# grbl-cnc3ax-nano.net
KiCad netlist of a schematic drawn in EAGLE
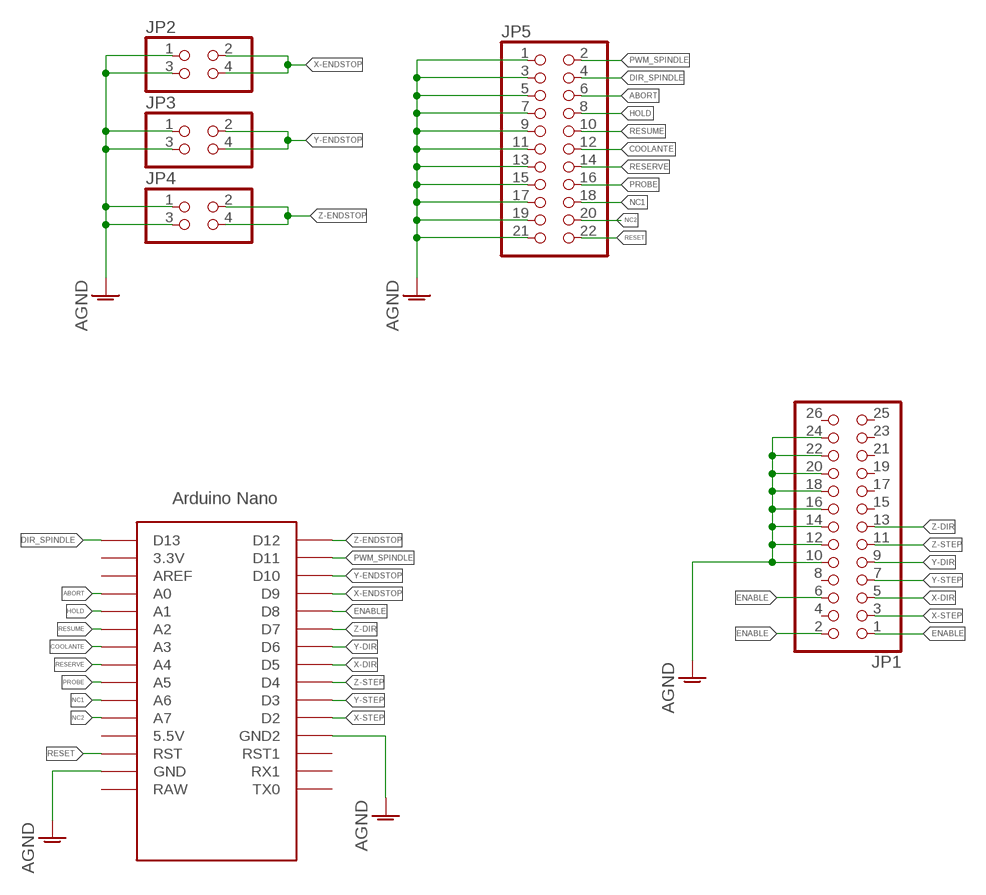
[diagram p0: schematic, sheet 1]

(export (version "E")
  (design (tool "Eeschema 10.0.6"))
  (components
    (comp (ref "JP1")
      (value "PINHD-2X13")
      (footprint "eagle-import:2X13")
      (libsource (lib "eagle-import") (part "PINHD-2X13"))
    )
    (comp (ref "JP2")
      (value "PINHD-2X2")
      (footprint "eagle-import:2X02")
      (libsource (lib "eagle-import") (part "PINHD-2X2"))
    )
    (comp (ref "JP3")
      (value "PINHD-2X2")
      (footprint "eagle-import:2X02")
      (libsource (lib "eagle-import") (part "PINHD-2X2"))
    )
    (comp (ref "JP4")
      (value "PINHD-2X2")
      (footprint "eagle-import:2X02")
      (libsource (lib "eagle-import") (part "PINHD-2X2"))
    )
    (comp (ref "JP5")
      (value "PINHD-2X11")
      (footprint "eagle-import:2X11")
      (libsource (lib "eagle-import") (part "PINHD-2X11"))
    )
    (comp (ref "U$1")
      (value "NANO")
      (footprint "eagle-import:NANO")
      (libsource (lib "eagle-import") (part "NANO"))
    )
  )
  (nets
    (net (code "1") (name "ABORT") (class "Default")
      (node (ref "JP5") (pin "6") (pinfunction "6_6") (pintype "passive"))
      (node (ref "U$1") (pin "A0") (pinfunction "A0_A0") (pintype "bidirectional"))
    )
    (net (code "2") (name "AGND") (class "Default")
      (node (ref "JP1") (pin "10") (pinfunction "10_10") (pintype "passive"))
      (node (ref "JP1") (pin "12") (pinfunction "12_12") (pintype "passive"))
      (node (ref "JP1") (pin "14") (pinfunction "14_14") (pintype "passive"))
      (node (ref "JP1") (pin "16") (pinfunction "16_16") (pintype "passive"))
      (node (ref "JP1") (pin "18") (pinfunction "18_18") (pintype "passive"))
      (node (ref "JP1") (pin "20") (pinfunction "20_20") (pintype "passive"))
      (node (ref "JP1") (pin "22") (pinfunction "22_22") (pintype "passive"))
      (node (ref "JP1") (pin "24") (pinfunction "24_24") (pintype "passive"))
      (node (ref "JP2") (pin "1") (pinfunction "1_1") (pintype "passive"))
      (node (ref "JP2") (pin "3") (pinfunction "3_3") (pintype "passive"))
      (node (ref "JP3") (pin "1") (pinfunction "1_1") (pintype "passive"))
      (node (ref "JP3") (pin "3") (pinfunction "3_3") (pintype "passive"))
      (node (ref "JP4") (pin "1") (pinfunction "1_1") (pintype "passive"))
      (node (ref "JP4") (pin "3") (pinfunction "3_3") (pintype "passive"))
      (node (ref "JP5") (pin "1") (pinfunction "1_1") (pintype "passive"))
      (node (ref "JP5") (pin "11") (pinfunction "11_11") (pintype "passive"))
      (node (ref "JP5") (pin "13") (pinfunction "13_13") (pintype "passive"))
      (node (ref "JP5") (pin "15") (pinfunction "15_15") (pintype "passive"))
      (node (ref "JP5") (pin "17") (pinfunction "17_17") (pintype "passive"))
      (node (ref "JP5") (pin "19") (pinfunction "19_19") (pintype "passive"))
      (node (ref "JP5") (pin "21") (pinfunction "21_21") (pintype "passive"))
      (node (ref "JP5") (pin "3") (pinfunction "3_3") (pintype "passive"))
      (node (ref "JP5") (pin "5") (pinfunction "5_5") (pintype "passive"))
      (node (ref "JP5") (pin "7") (pinfunction "7_7") (pintype "passive"))
      (node (ref "JP5") (pin "9") (pinfunction "9_9") (pintype "passive"))
      (node (ref "U$1") (pin "GND") (pinfunction "GND_GND") (pintype "bidirectional"))
      (node (ref "U$1") (pin "GND1") (pinfunction "GND2_GND1") (pintype "bidirectional"))
    )
    (net (code "3") (name "COOLANTE") (class "Default")
      (node (ref "JP5") (pin "12") (pinfunction "12_12") (pintype "passive"))
      (node (ref "U$1") (pin "A3") (pinfunction "A3_A3") (pintype "bidirectional"))
    )
    (net (code "4") (name "DIR_SPINDLE") (class "Default")
      (node (ref "JP5") (pin "4") (pinfunction "4_4") (pintype "passive"))
      (node (ref "U$1") (pin "D13") (pinfunction "D13_D13") (pintype "bidirectional"))
    )
    (net (code "5") (name "ENABLE") (class "Default")
      (node (ref "JP1") (pin "1") (pinfunction "1_1") (pintype "passive"))
      (node (ref "JP1") (pin "2") (pinfunction "2_2") (pintype "passive"))
      (node (ref "JP1") (pin "6") (pinfunction "6_6") (pintype "passive"))
      (node (ref "U$1") (pin "D8") (pinfunction "D8_D8") (pintype "bidirectional"))
    )
    (net (code "6") (name "HOLD") (class "Default")
      (node (ref "JP5") (pin "8") (pinfunction "8_8") (pintype "passive"))
      (node (ref "U$1") (pin "A1") (pinfunction "A1_A1") (pintype "bidirectional"))
    )
    (net (code "7") (name "NC1") (class "Default")
      (node (ref "JP5") (pin "18") (pinfunction "18_18") (pintype "passive"))
      (node (ref "U$1") (pin "A6") (pinfunction "A6_A6") (pintype "bidirectional"))
    )
    (net (code "8") (name "NC2") (class "Default")
      (node (ref "JP5") (pin "20") (pinfunction "20_20") (pintype "passive"))
      (node (ref "U$1") (pin "A7") (pinfunction "A7_A7") (pintype "bidirectional"))
    )
    (net (code "9") (name "PROBE") (class "Default")
      (node (ref "JP5") (pin "16") (pinfunction "16_16") (pintype "passive"))
      (node (ref "U$1") (pin "A5") (pinfunction "A5_A5") (pintype "bidirectional"))
    )
    (net (code "10") (name "PWM_SPINDLE") (class "Default")
      (node (ref "JP5") (pin "2") (pinfunction "2_2") (pintype "passive"))
      (node (ref "U$1") (pin "D11") (pinfunction "D11_D11") (pintype "bidirectional"))
    )
    (net (code "11") (name "RESERVE") (class "Default")
      (node (ref "JP5") (pin "14") (pinfunction "14_14") (pintype "passive"))
      (node (ref "U$1") (pin "A4") (pinfunction "A4_A4") (pintype "bidirectional"))
    )
    (net (code "12") (name "RESET") (class "Default")
      (node (ref "JP5") (pin "22") (pinfunction "22_22") (pintype "passive"))
      (node (ref "U$1") (pin "RST") (pinfunction "RST_RST") (pintype "bidirectional"))
    )
    (net (code "13") (name "RESUME") (class "Default")
      (node (ref "JP5") (pin "10") (pinfunction "10_10") (pintype "passive"))
      (node (ref "U$1") (pin "A2") (pinfunction "A2_A2") (pintype "bidirectional"))
    )
    (net (code "14") (name "X-DIR") (class "Default")
      (node (ref "JP1") (pin "5") (pinfunction "5_5") (pintype "passive"))
      (node (ref "U$1") (pin "D5") (pinfunction "D5_D5") (pintype "bidirectional"))
    )
    (net (code "15") (name "X-ENDSTOP") (class "Default")
      (node (ref "JP2") (pin "2") (pinfunction "2_2") (pintype "passive"))
      (node (ref "JP2") (pin "4") (pinfunction "4_4") (pintype "passive"))
      (node (ref "U$1") (pin "D9") (pinfunction "D9_D9") (pintype "bidirectional"))
    )
    (net (code "16") (name "X-STEP") (class "Default")
      (node (ref "JP1") (pin "3") (pinfunction "3_3") (pintype "passive"))
      (node (ref "U$1") (pin "D2") (pinfunction "D2_D2") (pintype "bidirectional"))
    )
    (net (code "17") (name "Y-DIR") (class "Default")
      (node (ref "JP1") (pin "9") (pinfunction "9_9") (pintype "passive"))
      (node (ref "U$1") (pin "D6") (pinfunction "D6_D6") (pintype "bidirectional"))
    )
    (net (code "18") (name "Y-ENDSTOP") (class "Default")
      (node (ref "JP3") (pin "2") (pinfunction "2_2") (pintype "passive"))
      (node (ref "JP3") (pin "4") (pinfunction "4_4") (pintype "passive"))
      (node (ref "U$1") (pin "D10") (pinfunction "D10_D10") (pintype "bidirectional"))
    )
    (net (code "19") (name "Y-STEP") (class "Default")
      (node (ref "JP1") (pin "7") (pinfunction "7_7") (pintype "passive"))
      (node (ref "U$1") (pin "D3") (pinfunction "D3_D3") (pintype "bidirectional"))
    )
    (net (code "20") (name "Z-DIR") (class "Default")
      (node (ref "JP1") (pin "13") (pinfunction "13_13") (pintype "passive"))
      (node (ref "U$1") (pin "D7") (pinfunction "D7_D7") (pintype "bidirectional"))
    )
    (net (code "21") (name "Z-ENDSTOP") (class "Default")
      (node (ref "JP4") (pin "2") (pinfunction "2_2") (pintype "passive"))
      (node (ref "JP4") (pin "4") (pinfunction "4_4") (pintype "passive"))
      (node (ref "U$1") (pin "D12") (pinfunction "D12_D12") (pintype "bidirectional"))
    )
    (net (code "22") (name "Z-STEP") (class "Default")
      (node (ref "JP1") (pin "11") (pinfunction "11_11") (pintype "passive"))
      (node (ref "U$1") (pin "D4") (pinfunction "D4_D4") (pintype "bidirectional"))
    )
    (net (code "23") (name "unconnected-(JP1-Pad4)") (class "Default")
      (node (ref "JP1") (pin "4") (pinfunction "4_4") (pintype "passive"))
    )
    (net (code "24") (name "unconnected-(JP1-Pad8)") (class "Default")
      (node (ref "JP1") (pin "8") (pinfunction "8_8") (pintype "passive"))
    )
    (net (code "25") (name "unconnected-(JP1-Pad15)") (class "Default")
      (node (ref "JP1") (pin "15") (pinfunction "15_15") (pintype "passive"))
    )
    (net (code "26") (name "unconnected-(JP1-Pad17)") (class "Default")
      (node (ref "JP1") (pin "17") (pinfunction "17_17") (pintype "passive"))
    )
    (net (code "27") (name "unconnected-(JP1-Pad19)") (class "Default")
      (node (ref "JP1") (pin "19") (pinfunction "19_19") (pintype "passive"))
    )
    (net (code "28") (name "unconnected-(JP1-Pad21)") (class "Default")
      (node (ref "JP1") (pin "21") (pinfunction "21_21") (pintype "passive"))
    )
    (net (code "29") (name "unconnected-(JP1-Pad23)") (class "Default")
      (node (ref "JP1") (pin "23") (pinfunction "23_23") (pintype "passive"))
    )
    (net (code "30") (name "unconnected-(JP1-Pad25)") (class "Default")
      (node (ref "JP1") (pin "25") (pinfunction "25_25") (pintype "passive"))
    )
    (net (code "31") (name "unconnected-(JP1-Pad26)") (class "Default")
      (node (ref "JP1") (pin "26") (pinfunction "26_26") (pintype "passive"))
    )
    (net (code "32") (name "unconnected-(U$1-5.5V-Pad5V)") (class "Default")
      (node (ref "U$1") (pin "5V") (pinfunction "5.5V_5V") (pintype "bidirectional"))
    )
    (net (code "33") (name "unconnected-(U$1-Pad3.3V)") (class "Default")
      (node (ref "U$1") (pin "3.3V") (pinfunction "3.3V_3.3V") (pintype "bidirectional"))
    )
    (net (code "34") (name "unconnected-(U$1-PadAREF)") (class "Default")
      (node (ref "U$1") (pin "AREF") (pinfunction "AREF_AREF") (pintype "bidirectional"))
    )
    (net (code "35") (name "unconnected-(U$1-PadICSP1)") (class "Default")
      (node (ref "U$1") (pin "ICSP1") (pinfunction "ICSP1_ICSP1") (pintype "bidirectional"))
    )
    (net (code "36") (name "unconnected-(U$1-PadICSP2)") (class "Default")
      (node (ref "U$1") (pin "ICSP2") (pinfunction "ICSP2_ICSP2") (pintype "bidirectional"))
    )
    (net (code "37") (name "unconnected-(U$1-PadICSP3)") (class "Default")
      (node (ref "U$1") (pin "ICSP3") (pinfunction "ICSP3_ICSP3") (pintype "bidirectional"))
    )
    (net (code "38") (name "unconnected-(U$1-PadICSP4)") (class "Default")
      (node (ref "U$1") (pin "ICSP4") (pinfunction "ICSP4_ICSP4") (pintype "bidirectional"))
    )
    (net (code "39") (name "unconnected-(U$1-PadICSP5)") (class "Default")
      (node (ref "U$1") (pin "ICSP5") (pinfunction "ICSP5_ICSP5") (pintype "bidirectional"))
    )
    (net (code "40") (name "unconnected-(U$1-PadICSP6)") (class "Default")
      (node (ref "U$1") (pin "ICSP6") (pinfunction "ICSP6_ICSP6") (pintype "bidirectional"))
    )
    (net (code "41") (name "unconnected-(U$1-PadRAW)") (class "Default")
      (node (ref "U$1") (pin "RAW") (pinfunction "RAW_RAW") (pintype "bidirectional"))
    )
    (net (code "42") (name "unconnected-(U$1-PadRST1)") (class "Default")
      (node (ref "U$1") (pin "RST1") (pinfunction "RST1_RST1") (pintype "bidirectional"))
    )
    (net (code "43") (name "unconnected-(U$1-PadRX1)") (class "Default")
      (node (ref "U$1") (pin "RX1") (pinfunction "RX1_RX1") (pintype "bidirectional"))
    )
    (net (code "44") (name "unconnected-(U$1-PadTX0)") (class "Default")
      (node (ref "U$1") (pin "TX0") (pinfunction "TX0_TX0") (pintype "bidirectional"))
    )
  )
)
